# Connector.net
KiCad netlist of a schematic drawn in Altium Designer
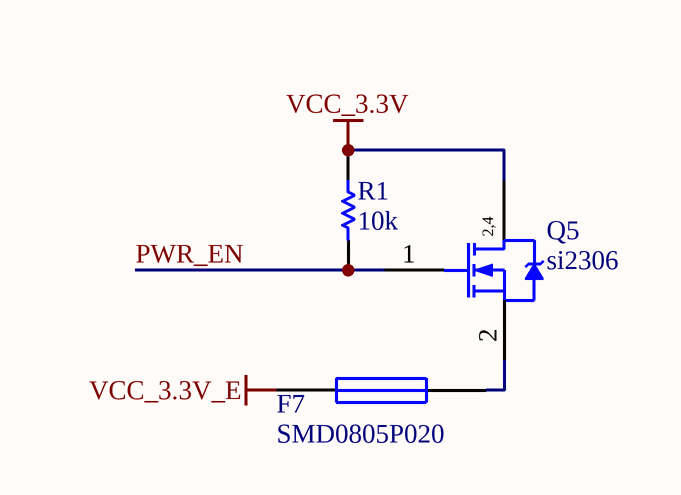
[diagram p0: Connector.SchDoc]

(export (version "E")
  (design (tool "Eeschema 10.0.6"))
  (components
    (comp (ref "F7")
      (value "SMD0805P020")
      (footprint "0805R")
      (description "Fuse")
      (fields (field (name "PUBLISHER") "Altium Limited"))
      (libsource (lib "Miscellaneous Devices") (part "Fuse 1"))
    )
    (comp (ref "Q5")
      (value "si2306")
      (footprint "SOT23-3")
      (description "BUK92150-55A")
      (fields (field (name "PUBLISHER") "Altium Limited"))
      (libsource (lib "Schlib1") (part "BUK92150-55A"))
    )
    (comp (ref "R1")
      (value "10k")
      (footprint "0603r")
      (description "Resistor")
      (fields (field (name "PUBLISHER") "Altium Limited"))
      (libsource (lib "Miscellaneous Devices") (part "Res1"))
    )
  )
  (nets
    (net (code "1") (name "/PWR_EN") (class "Default")
      (node (ref "Q5") (pin "1") (pinfunction "G_1") (pintype "passive"))
      (node (ref "R1") (pin "2") (pinfunction "2_2") (pintype "passive"))
    )
    (net (code "2") (name "Net-(Q5-S)") (class "Default")
      (node (ref "F7") (pin "2") (pinfunction "2_2") (pintype "passive"))
      (node (ref "Q5") (pin "2") (pinfunction "S_2") (pintype "passive"))
    )
    (net (code "3") (name "VCC_3.3V") (class "Default")
      (node (ref "Q5") (pin "3") (pinfunction "D_3") (pintype "passive"))
      (node (ref "R1") (pin "1") (pinfunction "1_1") (pintype "passive"))
    )
    (net (code "4") (name "VCC_3.3V_E") (class "Default")
      (node (ref "F7") (pin "1") (pinfunction "1_1") (pintype "passive"))
    )
  )
)
